# Power.net
KiCad netlist of a schematic drawn in Altium Designer
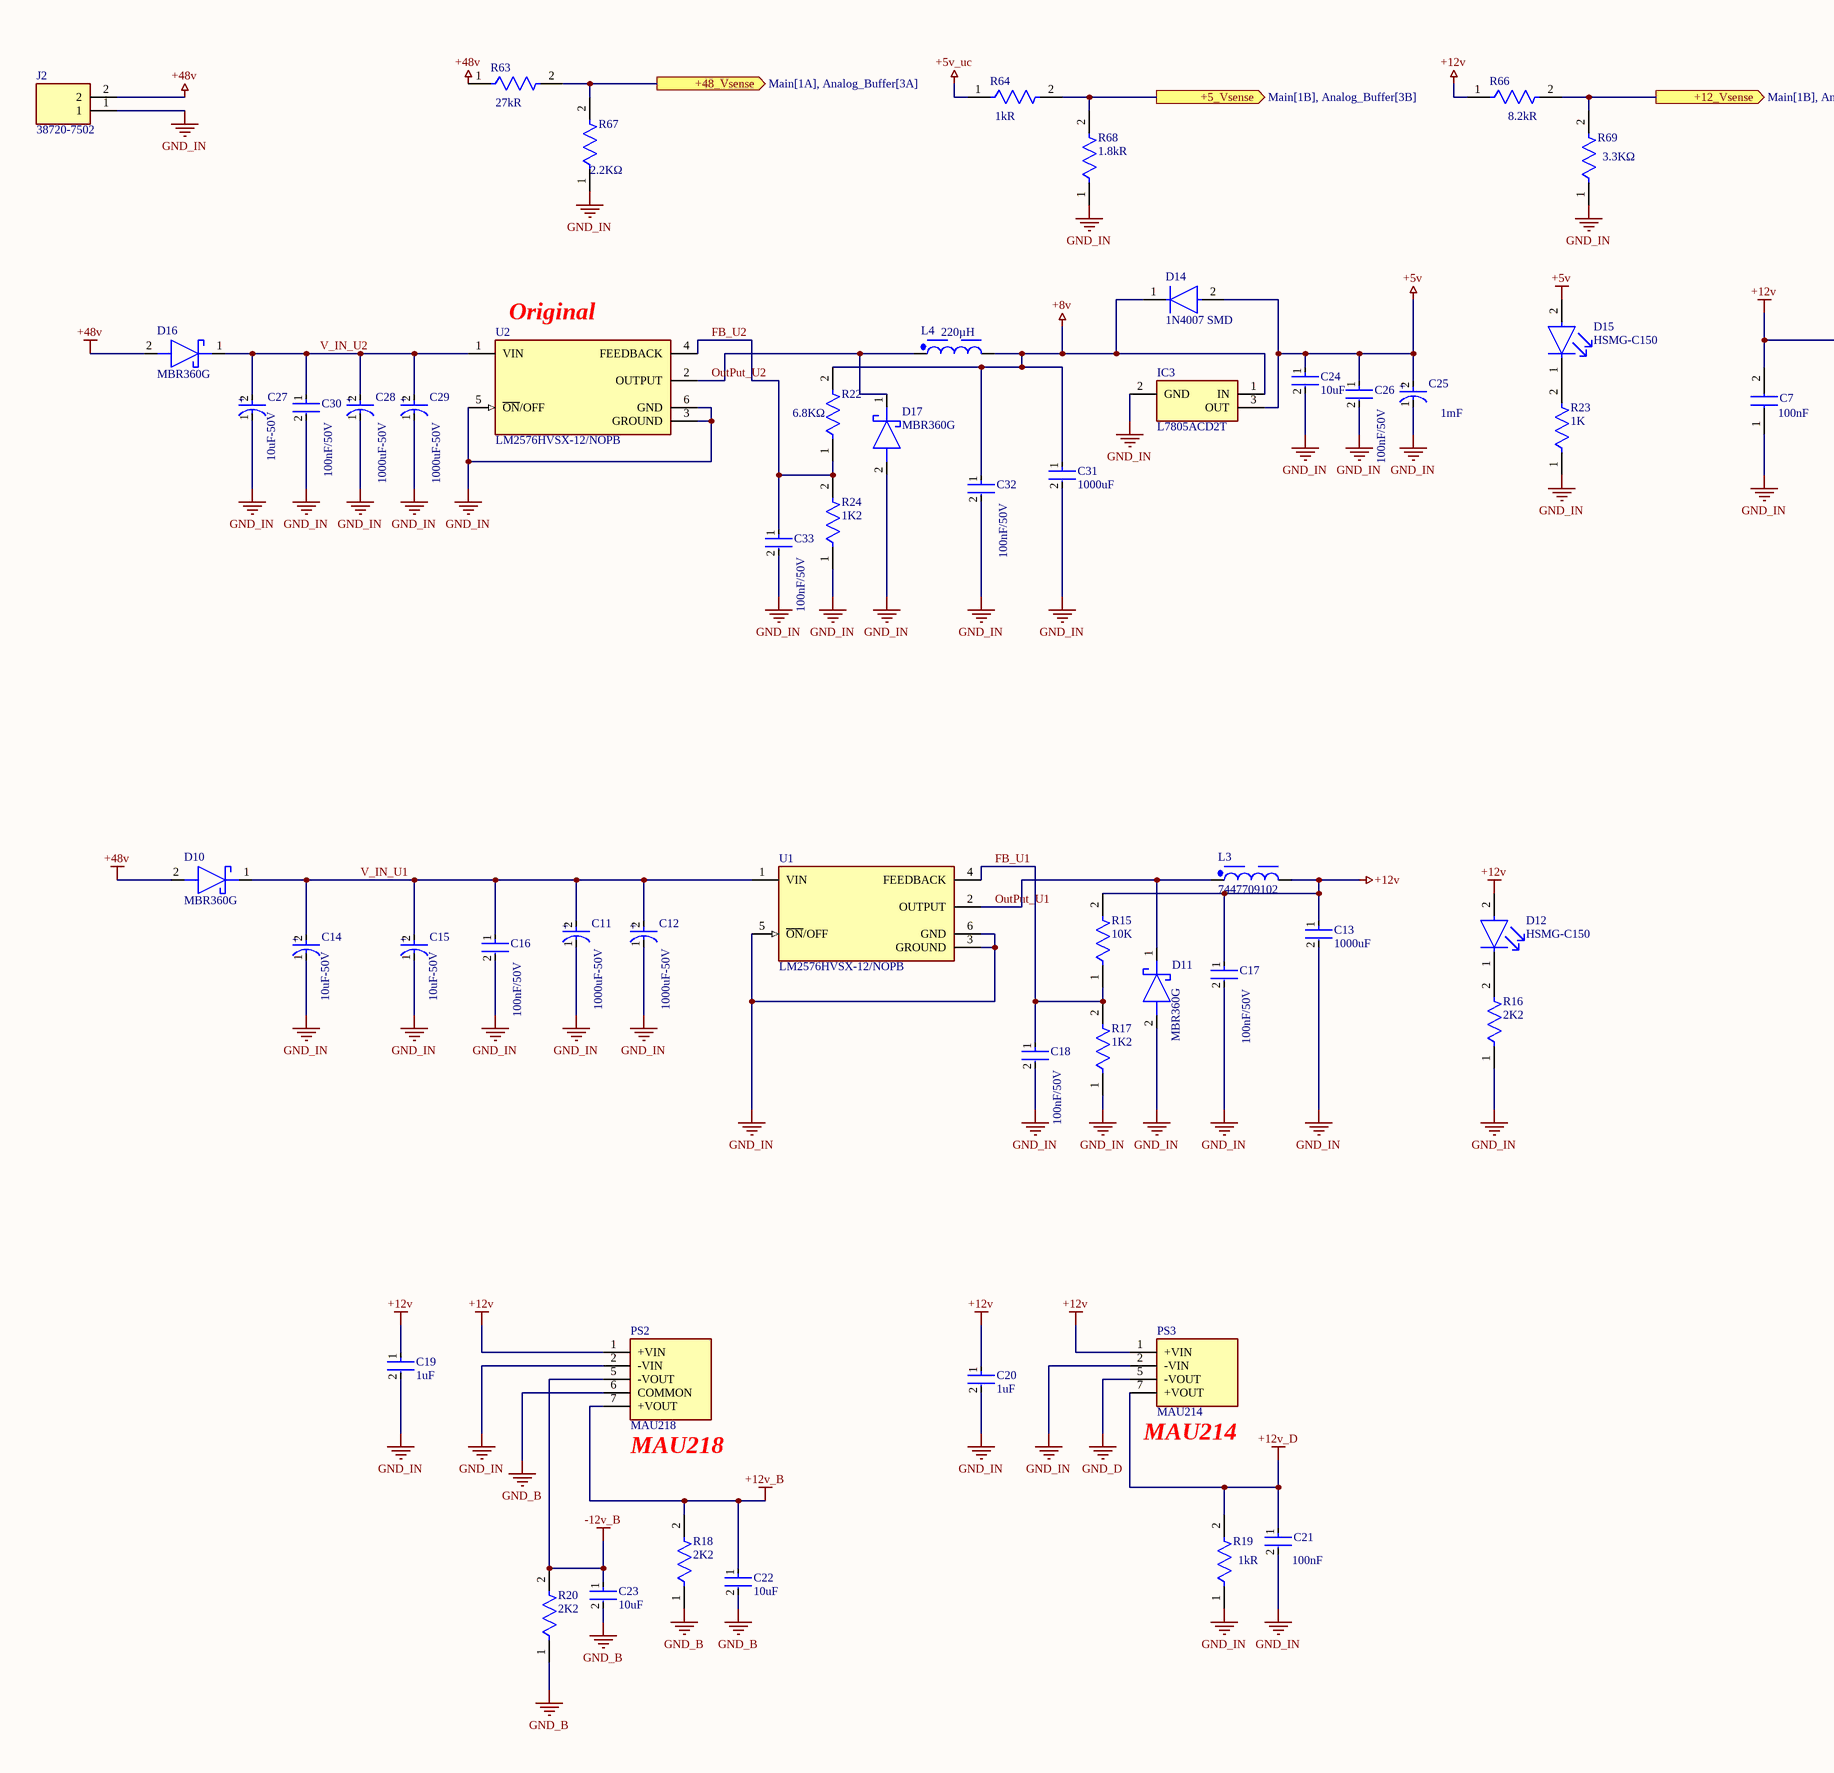
[diagram p0: Power.SchDoc, left]
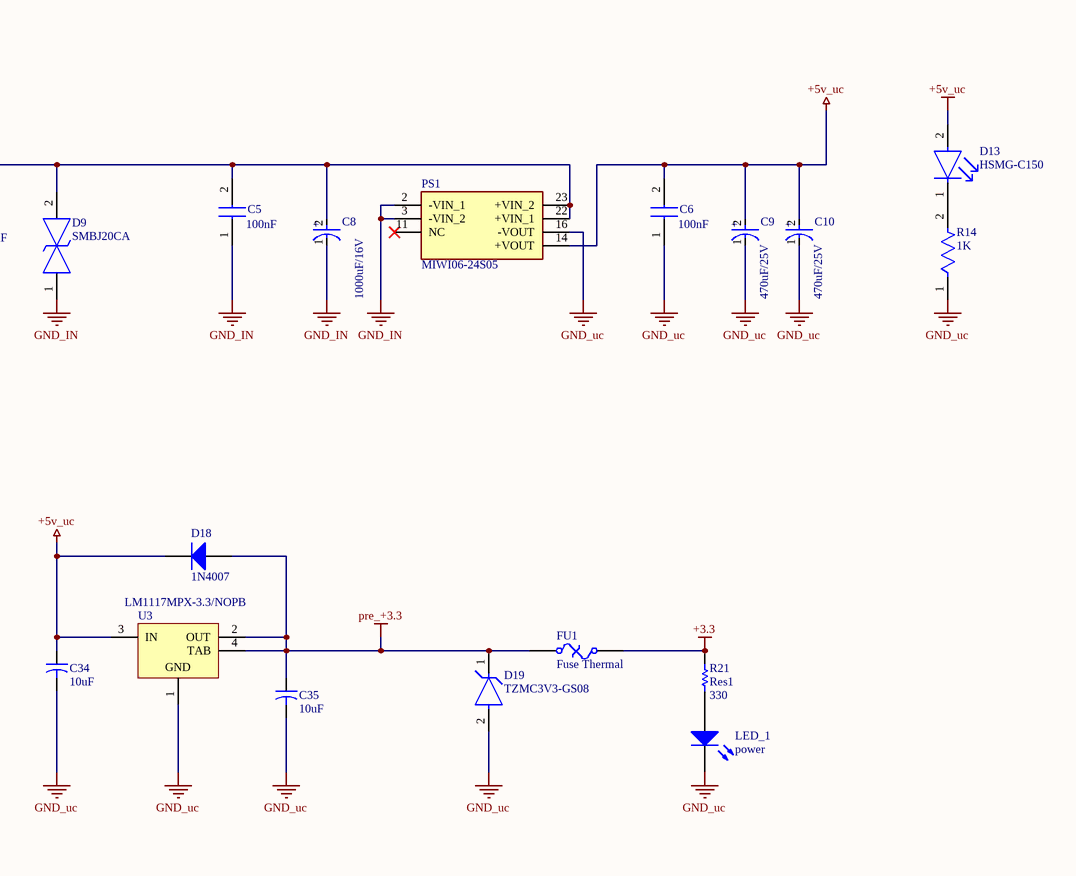
[diagram p1: Power.SchDoc, right]

(export (version "E")
  (design (tool "Eeschema 10.0.6"))
  (components
    (comp (ref "C5")
      (value "100nF")
      (footprint "SamacSys:CAPC3216X95N")
      (description "Capacitor")
      (fields
        (field (name "MANUFACTURER_PART_NUMBER") "GRM319F51H104ZA01D")
        (field (name "MOUSER PART NUMBER") "81-GRM319F51H104ZA")
      )
      (libsource (lib "*") (part "GRM319F51H104ZA01D"))
    )
    (comp (ref "C6")
      (value "100nF")
      (footprint "SamacSys:CAPC3216X95N")
      (description "Capacitor")
      (fields
        (field (name "MANUFACTURER_PART_NUMBER") "GRM319F51H104ZA01D")
        (field (name "MOUSER PART NUMBER") "81-GRM319F51H104ZA")
      )
      (libsource (lib "*") (part "GRM319F51H104ZA01D"))
    )
    (comp (ref "C7")
      (value "100nF")
      (footprint "SamacSys:CAPC3216X95N")
      (description "Capacitor")
      (fields
        (field (name "MANUFACTURER_PART_NUMBER") "GRM319F51H104ZA01D")
        (field (name "MOUSER PART NUMBER") "81-GRM319F51H104ZA")
      )
      (libsource (lib "*") (part "GRM319F51H104ZA01D"))
    )
    (comp (ref "C8")
      (value "1000uF/16V")
      (footprint "FP-FTG-MFG")
      (description "CAP ALUM 1000UF 20% 16V SMD")
      (fields (field (name "TOLERANCE") "20%") (field (name "VOLTAGE") "16V"))
      (libsource (lib "Altium Content Vault") (part "a00bbbee19879c290e62620ae7e47b1"))
    )
    (comp (ref "C9")
      (value "470uF/25V")
      (footprint "FP-FTF-MFG")
      (description "CAP ALUM 470UF 20% 25V SMD")
      (fields (field (name "VOLTAGE") "25V") (field (name "TOLERANCE") "20%"))
      (libsource (lib "Altium Content Vault") (part "a00bbbee19879c290e62620ae7e47b1"))
    )
    (comp (ref "C10")
      (value "470uF/25V")
      (footprint "FP-FTF-MFG")
      (description "CAP ALUM 470UF 20% 25V SMD")
      (fields (field (name "VOLTAGE") "25V") (field (name "TOLERANCE") "20%"))
      (libsource (lib "Altium Content Vault") (part "a00bbbee19879c290e62620ae7e47b1"))
    )
    (comp (ref "C11")
      (value "1000uF-50V")
      (footprint "FP-RAD-TH-D_12_5_0_5-L_25-MFG")
      (description "Aluminum Electrolytic Capacitors (Radial Lead Type) 1000uF ±20% 50V")
      (fields (field (name "TOLERANCE") "20%"))
      (libsource (lib "Altium Content Vault") (part "203bc49f2ac43e59fd269a8c329ed05"))
    )
    (comp (ref "C12")
      (value "1000uF-50V")
      (footprint "FP-RAD-TH-D_12_5_0_5-L_25-MFG")
      (description "Aluminum Electrolytic Capacitors (Radial Lead Type) 1000uF ±20% 50V")
      (fields (field (name "TOLERANCE") "20%"))
      (libsource (lib "Altium Content Vault") (part "203bc49f2ac43e59fd269a8c329ed05"))
    )
    (comp (ref "C13")
      (value "1000uF")
      (footprint "FP-C1206C-EB-MFG")
      (description "CAP CER 0.1UF 200V 10% X7R 1206")
      (fields (field (name "TOLERANCE") "0.1") (field (name "MANUFACTURER PART NUMBER") "C1206C104K2RACTU"))
      (libsource (lib "Altium Content Vault") (part "b4654b650e69147ec39a6b967a45e02"))
    )
    (comp (ref "C14")
      (value "10uF-50V")
      (footprint "FP-FKD-MFG")
      (description "CAP ALUM 10UF 20% 50V SMD")
      (fields (field (name "VOLTAGE") "50V") (field (name "TOLERANCE") "20%"))
      (libsource (lib "Altium Content Vault") (part "203bc49f2ac43e59fd269a8c329ed05"))
    )
    (comp (ref "C15")
      (value "10uF-50V")
      (footprint "FP-FKD-MFG")
      (description "CAP ALUM 10UF 20% 50V SMD")
      (fields (field (name "VOLTAGE") "50V") (field (name "TOLERANCE") "20%"))
      (libsource (lib "Altium Content Vault") (part "203bc49f2ac43e59fd269a8c329ed05"))
    )
    (comp (ref "C16")
      (value "100nF/50V")
      (footprint "FP-1206-L_3_2_0_2-W_1_6_0-MFG")
      (description "General Purpose Ceramic Capacitor, 1206, 100nF, 50V")
      (fields (field (name "TOLERANCE") "10%") (field (name "VOLTAGE") "50V"))
      (libsource (lib "Altium Content Vault") (part "02cd4be3c70576c341d710602a673aa"))
    )
    (comp (ref "C17")
      (value "100nF/50V")
      (footprint "FP-1206-L_3_2_0_2-W_1_6_0-MFG")
      (description "General Purpose Ceramic Capacitor, 1206, 100nF, 50V")
      (fields (field (name "TOLERANCE") "10%") (field (name "VOLTAGE") "50V"))
      (libsource (lib "Altium Content Vault") (part "02cd4be3c70576c341d710602a673aa"))
    )
    (comp (ref "C18")
      (value "100nF/50V")
      (footprint "FP-1206-L_3_2_0_2-W_1_6_0-MFG")
      (description "General Purpose Ceramic Capacitor, 1206, 100nF, 50V")
      (fields (field (name "TOLERANCE") "10%") (field (name "VOLTAGE") "50V"))
      (libsource (lib "Altium Content Vault") (part "02cd4be3c70576c341d710602a673aa"))
    )
    (comp (ref "C19")
      (value "1uF")
      (footprint "FP-1206-L_3_2_0_2-W_1_6_0-IPC_A")
      (description "General Purpose Ceramic Capacitor, 1206, 1uF, 10%, X7R, 15%, 50V")
      (fields (field (name "TOLERANCE") "10%") (field (name "VOLTAGE") "25V"))
      (libsource (lib "Altium Content Vault") (part "b4654b650e69147ec39a6b967a45e02"))
    )
    (comp (ref "C20")
      (value "1uF")
      (footprint "FP-1206-L_3_2_0_2-W_1_6_0-IPC_A")
      (description "General Purpose Ceramic Capacitor, 1206, 1uF, 10%, X7R, 15%, 50V")
      (fields (field (name "TOLERANCE") "10%") (field (name "VOLTAGE") "25V"))
      (libsource (lib "Altium Content Vault") (part "b4654b650e69147ec39a6b967a45e02"))
    )
    (comp (ref "C21")
      (value "12065C104KAT2A")
      (footprint "FP-1206-L_3_2_0_2-W_1_6_0-MFG")
      (description "General Purpose Ceramic Capacitor, 1206, 100nF, 10%, X7R, 15%, 50V")
      (fields
        (field (name "TOLERANCE") "10%")
        (field (name "VOLTAGE") "50V")
        (field (name "CAPACITANCE") "100nF")
      )
      (libsource (lib "Altium Content Vault") (part "02cd4be3c70576c341d710602a673aa"))
    )
    (comp (ref "C22")
      (value "10uF")
      (footprint "FP-GRM31C-0_2-e0_3_0_8-MFG")
      (description "Chip Multilayer Ceramic Capacitors for General Purpose, 1206, 10uF, X7R, 15%, 10%, 25V")
      (fields (field (name "TOLERANCE") "10%") (field (name "VOLTAGE") "25V"))
      (libsource (lib "Altium Content Vault") (part "02cd4be3c70576c341d710602a673aa"))
    )
    (comp (ref "C23")
      (value "10uF")
      (footprint "FP-GRM31C-0_2-e0_3_0_8-MFG")
      (description "Chip Multilayer Ceramic Capacitors for General Purpose, 1206, 10uF, X7R, 15%, 10%, 25V")
      (fields (field (name "TOLERANCE") "10%") (field (name "VOLTAGE") "25V"))
      (libsource (lib "Altium Content Vault") (part "02cd4be3c70576c341d710602a673aa"))
    )
    (comp (ref "C24")
      (value "10uF")
      (footprint "FP-GRM31C-0_2-e0_3_0_8-MFG")
      (description "Chip Multilayer Ceramic Capacitors for General Purpose, 1206, 10uF, X7R, 15%, 10%, 25V")
      (fields (field (name "TOLERANCE") "10%") (field (name "VOLTAGE") "25V"))
      (libsource (lib "Altium Content Vault") (part "02cd4be3c70576c341d710602a673aa"))
    )
    (comp (ref "C25")
      (value "EEEFT1C102AP")
      (footprint "FP-FTG-MFG")
      (description "CAP ALUM 1000UF 20% 16V SMD")
      (fields
        (field (name "TOLERANCE") "20%")
        (field (name "CAPACITANCE") "1mF")
        (field (name "VOLTAGE") "16V")
      )
      (libsource (lib "Altium Content Vault") (part "a00bbbee19879c290e62620ae7e47b1"))
    )
    (comp (ref "C26")
      (value "100nF/50V")
      (footprint "FP-1206-L_3_2_0_2-W_1_6_0-MFG")
      (description "General Purpose Ceramic Capacitor, 1206, 100nF, 50V")
      (fields (field (name "TOLERANCE") "10%") (field (name "VOLTAGE") "50V"))
      (libsource (lib "Altium Content Vault") (part "02cd4be3c70576c341d710602a673aa"))
    )
    (comp (ref "C27")
      (value "10uF-50V")
      (footprint "FP-FKD-MFG")
      (description "CAP ALUM 10UF 20% 50V SMD")
      (fields (field (name "VOLTAGE") "50V") (field (name "TOLERANCE") "20%"))
      (libsource (lib "Altium Content Vault") (part "203bc49f2ac43e59fd269a8c329ed05"))
    )
    (comp (ref "C28")
      (value "1000uF-50V")
      (footprint "FP-RAD-TH-D_12_5_0_5-L_25-MFG")
      (description "Aluminum Electrolytic Capacitors (Radial Lead Type) 1000uF ±20% 50V")
      (fields (field (name "TOLERANCE") "20%"))
      (libsource (lib "Altium Content Vault") (part "203bc49f2ac43e59fd269a8c329ed05"))
    )
    (comp (ref "C29")
      (value "1000uF-50V")
      (footprint "FP-RAD-TH-D_12_5_0_5-L_25-MFG")
      (description "Aluminum Electrolytic Capacitors (Radial Lead Type) 1000uF ±20% 50V")
      (fields (field (name "TOLERANCE") "20%"))
      (libsource (lib "Altium Content Vault") (part "203bc49f2ac43e59fd269a8c329ed05"))
    )
    (comp (ref "C30")
      (value "100nF/50V")
      (footprint "FP-1206-L_3_2_0_2-W_1_6_0-MFG")
      (description "General Purpose Ceramic Capacitor, 1206, 100nF, 50V")
      (fields (field (name "TOLERANCE") "10%") (field (name "VOLTAGE") "50V"))
      (libsource (lib "Altium Content Vault") (part "02cd4be3c70576c341d710602a673aa"))
    )
    (comp (ref "C31")
      (value "1000uF")
      (footprint "FP-C1206C-EB-MFG")
      (description "CAP CER 0.1UF 200V 10% X7R 1206")
      (fields (field (name "TOLERANCE") "0.1") (field (name "MANUFACTURER PART NUMBER") "C1206C104K2RACTU"))
      (libsource (lib "Altium Content Vault") (part "b4654b650e69147ec39a6b967a45e02"))
    )
    (comp (ref "C32")
      (value "100nF/50V")
      (footprint "FP-1206-L_3_2_0_2-W_1_6_0-MFG")
      (description "General Purpose Ceramic Capacitor, 1206, 100nF, 50V")
      (fields (field (name "TOLERANCE") "10%") (field (name "VOLTAGE") "50V"))
      (libsource (lib "Altium Content Vault") (part "02cd4be3c70576c341d710602a673aa"))
    )
    (comp (ref "C33")
      (value "100nF/50V")
      (footprint "FP-1206-L_3_2_0_2-W_1_6_0-MFG")
      (description "General Purpose Ceramic Capacitor, 1206, 100nF, 50V")
      (fields (field (name "TOLERANCE") "10%") (field (name "VOLTAGE") "50V"))
      (libsource (lib "Altium Content Vault") (part "02cd4be3c70576c341d710602a673aa"))
    )
    (comp (ref "C34")
      (value "10uF")
      (footprint "0805C")
      (description "Capacitor")
      (fields (field (name "Comment") "Cap_El") (field (name "PUBLISHER") "Altium Limited"))
      (libsource (lib "KN2CLib") (part "Cap_El"))
    )
    (comp (ref "C35")
      (value "10uF")
      (footprint "0805C")
      (description "Capacitor")
      (fields (field (name "Comment") "Cap_El") (field (name "PUBLISHER") "Altium Limited"))
      (libsource (lib "KN2CLib") (part "Cap_El"))
    )
    (comp (ref "D9")
      (value "SMBJ20CA")
      (footprint "SamacSys:DIOM5336X245N")
      (description "TVS Diode (Bi-directional)")
      (fields (field (name "MOUSER PART NUMBER") "512-SMBJ20CA"))
      (libsource (lib "*") (part "SMBJ20CA"))
    )
    (comp (ref "D10")
      (value "MBR360G")
      (footprint "SamacSys:DIOAD2860W130L840D505")
      (description "Schottky Diode")
      (fields (field (name "MOUSER PART NUMBER") "863-MBR360G"))
      (libsource (lib "*") (part "MBR360G"))
    )
    (comp (ref "D11")
      (value "MBR360G")
      (footprint "SamacSys:DIOAD2860W130L840D505")
      (description "Schottky Diode")
      (fields (field (name "MOUSER PART NUMBER") "863-MBR360G"))
      (libsource (lib "*") (part "MBR360G"))
    )
    (comp (ref "D12")
      (value "HSMG-C150")
      (footprint "FP-HSMG-C150-MFG")
      (description "LED GREEN DIFFUSED 1206 SMD")
      (fields
        (field (name "MANUFACTURER") "Broadcom")
        (field (name "OCTOPART") "https://octopart.com/hsmg-c150-broadcom-71131304")
      )
      (libsource (lib "Altium Content Vault") (part "8706943c75ba83719d021d2fdc84c58"))
    )
    (comp (ref "D13")
      (value "HSMG-C150")
      (footprint "FP-HSMG-C150-MFG")
      (description "LED GREEN DIFFUSED 1206 SMD")
      (fields
        (field (name "MANUFACTURER") "Broadcom")
        (field (name "OCTOPART") "https://octopart.com/hsmg-c150-broadcom-71131304")
      )
      (libsource (lib "Altium Content Vault") (part "8706943c75ba83719d021d2fdc84c58"))
    )
    (comp (ref "D14")
      (value "1N4007 SMD")
      (footprint "FP-1N4007_SMD-IPC_C")
      (description "Rectifier, 1Kv, 1A, Do-214Ac Rohs Compliant: Yes")
      (libsource (lib "Altium Content Vault") (part "d7152d700b627762746794eb795d46e"))
    )
    (comp (ref "D15")
      (value "HSMG-C150")
      (footprint "FP-HSMG-C150-MFG")
      (description "LED GREEN DIFFUSED 1206 SMD")
      (fields
        (field (name "MANUFACTURER") "Broadcom")
        (field (name "OCTOPART") "https://octopart.com/hsmg-c150-broadcom-71131304")
      )
      (libsource (lib "Altium Content Vault") (part "8706943c75ba83719d021d2fdc84c58"))
    )
    (comp (ref "D16")
      (value "MBR360G")
      (footprint "SamacSys:DIOAD2860W130L840D505")
      (description "Schottky Diode")
      (fields (field (name "MOUSER PART NUMBER") "863-MBR360G"))
      (libsource (lib "*") (part "MBR360G"))
    )
    (comp (ref "D17")
      (value "MBR360G")
      (footprint "SamacSys:DIOAD2860W130L840D505")
      (description "Schottky Diode")
      (fields (field (name "MOUSER PART NUMBER") "863-MBR360G"))
      (libsource (lib "*") (part "MBR360G"))
    )
    (comp (ref "D18")
      (value "1N4007")
      (footprint "430X270D")
      (description "1 Amp General Purpose Rectifier")
      (fields (field (name "PUBLISHER") "Altium Limited"))
      (libsource (lib "KN2CLib") (part "Diode"))
    )
    (comp (ref "D19")
      (value "TZMC3V3-GS08")
      (footprint "FP-6_560-5005_01-4-MFG")
      (description "DIODE ZENER 3.3V 500MW SOD80")
      (fields
        (field (name "MANUFACTURER") "Vishay")
        (field (name "OCTOPART") "https://octopart.com/tzmc3v3-gs08-vishay-55388698")
      )
      (libsource (lib "Altium Content Vault") (part "f813f71cba58e380607f5dd3caf9714"))
    )
    (comp (ref "FU1")
      (value "Fuse Thermal")
      (footprint "1206")
      (description "Thermal Fuse")
      (fields (field (name "PUBLISHER") "Altium Limited"))
      (libsource (lib "Miscellaneous Devices") (part "Fuse Thermal"))
    )
    (comp (ref "IC3")
      (value "L7805ACD2T")
      (footprint "SamacSys:STB20N95K5")
      (description "Integrated Circuit")
      (fields (field (name "MOUSER PART NUMBER") "511-L7805ACD2T"))
      (libsource (lib "*") (part "L7805ACD2T"))
    )
    (comp (ref "J2")
      (value "38720-7502")
      (footprint "SamacSys:387207502")
      (description "Connector")
      (fields (field (name "MOUSER PART NUMBER") "538-38720-7502"))
      (libsource (lib "*") (part "38720-7502"))
    )
    (comp (ref "L3")
      (value "7447709102")
      (footprint "WE-PD_1210")
      (fields (field (name "TOLERANCE") "20%"))
      (libsource (lib "Altium Content Vault") (part "Inductor - 2"))
    )
    (comp (ref "L4")
      (value "7447709221")
      (footprint "WE-PD_1210")
      (fields (field (name "INDUCTANCE") "220µH") (field (name "TOLERANCE") "20%"))
      (libsource (lib "Altium Content Vault") (part "Inductor - 2"))
    )
    (comp (ref "LED_1")
      (value "power")
      (footprint "0805LED")
      (description "Typical BLUE SiC LED")
      (fields (field (name "PUBLISHER") "Altium Limited"))
      (libsource (lib "Miscellaneous Devices") (part "LED3"))
    )
    (comp (ref "PS1")
      (value "MIWI06-24S05")
      (footprint "SamacSys:MIWI06_S")
      (description "Power Supply")
      (libsource (lib "*") (part "MIWI06-24S05"))
    )
    (comp (ref "PS2")
      (value "MAU218")
      (footprint "SamacSys:MAU218")
      (description "Power Supply")
      (libsource (lib "*") (part "MAU218"))
    )
    (comp (ref "PS3")
      (value "MAU214")
      (footprint "SamacSys:MAU214")
      (description "Power Supply")
      (libsource (lib "*") (part "MAU214"))
    )
    (comp (ref "R14")
      (value "1K")
      (footprint "FP-CR1206-IPC_A")
      (description "Thick Film Chip Resistors 1206 1kΩ 0.25W 1% 100ppm/°C")
      (fields (field (name "TOLERANCE") "1%"))
      (libsource (lib "Altium Content Vault") (part "1029c3af85768c4190bb7ad29bc67b5"))
    )
    (comp (ref "R15")
      (value "10K")
      (footprint "FP-CRCW1206-e3-IPC_C")
      (description "RES Thick Film, 10kΩ, 1%, 0.25W, 100ppm/°C, 1206")
      (fields (field (name "TOLERANCE") "1%"))
      (libsource (lib "Altium Content Vault") (part "1029c3af85768c4190bb7ad29bc67b5"))
    )
    (comp (ref "R16")
      (value "2K2")
      (footprint "FP-CRGCQ1206-IPC_C")
      (description "CRGCQ 1206 2K2 5%")
      (fields (field (name "TOLERANCE") "0.05") (field (name "MANUFACTURER PART NUMBER") "CRGCQ1206J2K2"))
      (libsource (lib "Altium Content Vault") (part "1029c3af85768c4190bb7ad29bc67b5"))
    )
    (comp (ref "R17")
      (value "1K2")
      (footprint "FP-CRGCQ1206-IPC_C")
      (description "CRGCQ 1206 1K2 1%")
      (fields
        (field (name "MANUFACTURER") "TE Connectivity")
        (field (name "OCTOPART") "https://octopart.com/crgcq1206f1k2-te+connectivity-91018259")
      )
      (libsource (lib "Altium Content Vault") (part "1029c3af85768c4190bb7ad29bc67b5"))
    )
    (comp (ref "R18")
      (value "2K2")
      (footprint "FP-CRGCQ1206-IPC_C")
      (description "CRGCQ 1206 2K2 5%")
      (fields (field (name "TOLERANCE") "0.05") (field (name "MANUFACTURER PART NUMBER") "CRGCQ1206J2K2"))
      (libsource (lib "Altium Content Vault") (part "1029c3af85768c4190bb7ad29bc67b5"))
    )
    (comp (ref "R19")
      (value "CR1206-FX-1001ELF")
      (footprint "FP-CR1206-IPC_A")
      (description "Thick Film Chip Resistors 1206 1kΩ 0.25W 1% 100ppm/°C")
      (fields (field (name "TOLERANCE") "1%") (field (name "RESISTANCE") "1kR"))
      (libsource (lib "Altium Content Vault") (part "1029c3af85768c4190bb7ad29bc67b5"))
    )
    (comp (ref "R20")
      (value "2K2")
      (footprint "FP-CRGCQ1206-IPC_C")
      (description "CRGCQ 1206 2K2 5%")
      (fields (field (name "TOLERANCE") "0.05") (field (name "MANUFACTURER PART NUMBER") "CRGCQ1206J2K2"))
      (libsource (lib "Altium Content Vault") (part "1029c3af85768c4190bb7ad29bc67b5"))
    )
    (comp (ref "R21")
      (value "Res1")
      (footprint "0805L")
      (description "Resistor")
      (fields (field (name "ALTIUM_VALUE") "330") (field (name "PUBLISHER") "Altium Limited"))
      (libsource (lib "Miscellaneous Devices") (part "Res1"))
    )
    (comp (ref "R22")
      (value "6.8KΩ")
      (footprint "FP-CRGCQ1206-IPC_C")
      (description "CRGCQ1206 6.8KΩ 0.25W 5% ±100ppm/°C 200V")
      (fields
        (field (name "TOLERANCE") "0.05")
        (field (name "OCTOPART") "https://octopart.com/crgcq1206j6k8-te+connectivity-91018343")
      )
      (libsource (lib "Altium Content Vault") (part "1029c3af85768c4190bb7ad29bc67b5"))
    )
    (comp (ref "R23")
      (value "1K")
      (footprint "FP-CR1206-IPC_A")
      (description "Thick Film Chip Resistors 1206 1kΩ 0.25W 1% 100ppm/°C")
      (fields (field (name "TOLERANCE") "1%"))
      (libsource (lib "Altium Content Vault") (part "1029c3af85768c4190bb7ad29bc67b5"))
    )
    (comp (ref "R24")
      (value "1K2")
      (footprint "FP-CRGCQ1206-IPC_C")
      (description "CRGCQ 1206 1K2 1%")
      (fields
        (field (name "MANUFACTURER") "TE Connectivity")
        (field (name "OCTOPART") "https://octopart.com/crgcq1206f1k2-te+connectivity-91018259")
      )
      (libsource (lib "Altium Content Vault") (part "1029c3af85768c4190bb7ad29bc67b5"))
    )
    (comp (ref "R63")
      (value "RC3216J273CS")
      (footprint "FP-RC3216-IPC_A")
      (description "Res Thick Film 1206 27kΩ 5% 0.25W ±100ppm/°C Molded SMD T/R")
      (fields (field (name "TOLERANCE") "5%") (field (name "RESISTANCE") "27kR"))
      (libsource (lib "Altium Content Vault") (part "1029c3af85768c4190bb7ad29bc67b5"))
    )
    (comp (ref "R64")
      (value "CR1206-FX-1001ELF")
      (footprint "FP-CR1206-IPC_A")
      (description "Thick Film Chip Resistors 1206 1kΩ 0.25W 1% 100ppm/°C")
      (fields (field (name "TOLERANCE") "1%") (field (name "RESISTANCE") "1kR"))
      (libsource (lib "Altium Content Vault") (part "1029c3af85768c4190bb7ad29bc67b5"))
    )
    (comp (ref "R66")
      (value "CRCW12068K20FKEA")
      (footprint "FP-CRCW1206-e3-IPC_A")
      (description "RES Thick Film, 8.2kΩ, 1%, 0.25W, 100ppm/°C, 1206")
      (fields (field (name "TOLERANCE") "1%") (field (name "RESISTANCE") "8.2kR"))
      (libsource (lib "Altium Content Vault") (part "1029c3af85768c4190bb7ad29bc67b5"))
    )
    (comp (ref "R67")
      (value "2.2KΩ")
      (footprint "FP-CRGCQ1206-IPC_C")
      (description "CRGCQ 1206 2K2 5%")
      (fields (field (name "TOLERANCE") "0.05") (field (name "MANUFACTURER PART NUMBER") "CRGCQ1206J2K2"))
      (libsource (lib "Altium Content Vault") (part "1029c3af85768c4190bb7ad29bc67b5"))
    )
    (comp (ref "R68")
      (value "CRCW12061K80FKEA")
      (footprint "FP-CRCW1206-e3-IPC_B")
      (description "RES Thick Film, 1.8kΩ, 1%, 0.25W, 100ppm/°C, 1206")
      (fields (field (name "RESISTANCE") "1.8kR") (field (name "TOLERANCE") "1%"))
      (libsource (lib "Altium Content Vault") (part "1029c3af85768c4190bb7ad29bc67b5"))
    )
    (comp (ref "R69")
      (value "3.3KΩ")
      (footprint "FP-CRGCQ1206-IPC_C")
      (description "CRGCQ1206 3.3KΩ 0.25W 5% ±100ppm/°C 200V")
      (fields
        (field (name "OCTOPART") "https://octopart.com/crgcq1206j3k3-te+connectivity-91018329")
        (field (name "MANUFACTURER PART NUMBER") "CRGCQ1206J3K3")
      )
      (libsource (lib "Altium Content Vault") (part "1029c3af85768c4190bb7ad29bc67b5"))
    )
    (comp (ref "U1")
      (value "LM2576HVSX-12/NOPB")
      (footprint "FP-KTT0005B-MFG")
      (description "IC REG BUCK 12V 3A TO263-5")
      (libsource (lib "Altium Content Vault") (part "970efae79796d18f90998b1df728a7c"))
    )
    (comp (ref "U2")
      (value "LM2576HVSX-12/NOPB")
      (footprint "FP-KTT0005B-MFG")
      (description "IC REG BUCK 12V 3A TO263-5")
      (libsource (lib "Altium Content Vault") (part "970efae79796d18f90998b1df728a7c"))
    )
    (comp (ref "U3")
      (value "LM1117MPX-3.3/NOPB")
      (footprint "DCY0004A_L")
      (description "800mA Low-Dropout Linear Regulator, 4-pin SOT-223, Pb-Free")
      (fields (field (name "MANUFACTURER") "Texas Instruments"))
      (libsource (lib "Altium Content Vault") (part "PM-REG-LM1086-SOT4"))
    )
  )
  (nets
    (net (code "1") (name "+3.3") (class "Default")
      (node (ref "FU1") (pin "2") (pinfunction "2_2") (pintype "passive"))
      (node (ref "R21") (pin "1") (pinfunction "1_1") (pintype "passive"))
    )
    (net (code "2") (name "+5v") (class "Default")
      (node (ref "C24") (pin "1") (pinfunction "1_1") (pintype "passive"))
      (node (ref "C25") (pin "2") (pinfunction "A_2") (pintype "passive"))
      (node (ref "C26") (pin "1") (pinfunction "1_1") (pintype "passive"))
      (node (ref "D14") (pin "2") (pinfunction "A_2") (pintype "passive"))
      (node (ref "D15") (pin "2") (pinfunction "A_2") (pintype "passive"))
      (node (ref "IC3") (pin "3") (pinfunction "OUT_3") (pintype "passive"))
    )
    (net (code "3") (name "+5v_uc") (class "Default")
      (node (ref "C10") (pin "2") (pinfunction "A_2") (pintype "passive"))
      (node (ref "C34") (pin "1") (pinfunction "1_1") (pintype "passive"))
      (node (ref "C6") (pin "2") (pinfunction "2_2") (pintype "passive"))
      (node (ref "C9") (pin "2") (pinfunction "A_2") (pintype "passive"))
      (node (ref "D13") (pin "2") (pinfunction "A_2") (pintype "passive"))
      (node (ref "D18") (pin "2") (pinfunction "K_2") (pintype "passive"))
      (node (ref "PS1") (pin "14") (pinfunction "+VOUT_14") (pintype "passive"))
      (node (ref "R64") (pin "1") (pinfunction "1_1") (pintype "passive"))
      (node (ref "U3") (pin "3") (pinfunction "IN_3") (pintype "power_in"))
    )
    (net (code "4") (name "+8v") (class "Default")
      (node (ref "C31") (pin "1") (pinfunction "1_1") (pintype "passive"))
      (node (ref "C32") (pin "1") (pinfunction "1_1") (pintype "passive"))
      (node (ref "D14") (pin "1") (pinfunction "C_1") (pintype "passive"))
      (node (ref "IC3") (pin "1") (pinfunction "IN_1") (pintype "passive"))
      (node (ref "L4") (pin "2") (pinfunction "2_2") (pintype "passive"))
      (node (ref "R22") (pin "2") (pinfunction "2_2") (pintype "passive"))
    )
    (net (code "5") (name "+12v") (class "Default")
      (node (ref "C13") (pin "1") (pinfunction "1_1") (pintype "passive"))
      (node (ref "C17") (pin "1") (pinfunction "1_1") (pintype "passive"))
      (node (ref "C19") (pin "1") (pinfunction "1_1") (pintype "passive"))
      (node (ref "C20") (pin "1") (pinfunction "1_1") (pintype "passive"))
      (node (ref "C5") (pin "2") (pinfunction "2_2") (pintype "passive"))
      (node (ref "C7") (pin "2") (pinfunction "2_2") (pintype "passive"))
      (node (ref "C8") (pin "2") (pinfunction "A_2") (pintype "passive"))
      (node (ref "D12") (pin "2") (pinfunction "A_2") (pintype "passive"))
      (node (ref "D9") (pin "2") (pinfunction "2_2") (pintype "passive"))
      (node (ref "L3") (pin "2") (pinfunction "2_2") (pintype "passive"))
      (node (ref "PS1") (pin "22") (pinfunction "+VIN_1_22") (pintype "passive"))
      (node (ref "PS1") (pin "23") (pinfunction "+VIN_2_23") (pintype "passive"))
      (node (ref "PS2") (pin "1") (pinfunction "+VIN_1") (pintype "passive"))
      (node (ref "PS3") (pin "1") (pinfunction "+VIN_1") (pintype "passive"))
      (node (ref "R15") (pin "2") (pinfunction "2_2") (pintype "passive"))
      (node (ref "R66") (pin "1") (pinfunction "1_1") (pintype "passive"))
    )
    (net (code "6") (name "+12v_B") (class "Default")
      (node (ref "C22") (pin "1") (pinfunction "1_1") (pintype "passive"))
      (node (ref "PS2") (pin "7") (pinfunction "+VOUT_7") (pintype "passive"))
      (node (ref "R18") (pin "2") (pinfunction "2_2") (pintype "passive"))
    )
    (net (code "7") (name "+12v_D") (class "Default")
      (node (ref "C21") (pin "1") (pinfunction "1_1") (pintype "passive"))
      (node (ref "PS3") (pin "7") (pinfunction "+VOUT_7") (pintype "passive"))
      (node (ref "R19") (pin "2") (pinfunction "2_2") (pintype "passive"))
    )
    (net (code "8") (name "+48v") (class "Default")
      (node (ref "D10") (pin "2") (pinfunction "A_2") (pintype "passive"))
      (node (ref "D16") (pin "2") (pinfunction "A_2") (pintype "passive"))
      (node (ref "J2") (pin "2") (pinfunction "2_2") (pintype "passive"))
      (node (ref "R63") (pin "1") (pinfunction "1_1") (pintype "passive"))
    )
    (net (code "9") (name "-12v_B") (class "Default")
      (node (ref "C23") (pin "1") (pinfunction "1_1") (pintype "passive"))
      (node (ref "PS2") (pin "5") (pinfunction "-VOUT_5") (pintype "passive"))
      (node (ref "R20") (pin "2") (pinfunction "2_2") (pintype "passive"))
    )
    (net (code "10") (name "/+5_Vsense") (class "Default")
      (node (ref "R64") (pin "2") (pinfunction "2_2") (pintype "passive"))
      (node (ref "R68") (pin "2") (pinfunction "2_2") (pintype "passive"))
    )
    (net (code "11") (name "/+12_Vsense") (class "Default")
      (node (ref "R66") (pin "2") (pinfunction "2_2") (pintype "passive"))
      (node (ref "R69") (pin "2") (pinfunction "2_2") (pintype "passive"))
    )
    (net (code "12") (name "/+48_Vsense") (class "Default")
      (node (ref "R63") (pin "2") (pinfunction "2_2") (pintype "passive"))
      (node (ref "R67") (pin "2") (pinfunction "2_2") (pintype "passive"))
    )
    (net (code "13") (name "/FB_U1") (class "Default")
      (node (ref "C18") (pin "1") (pinfunction "1_1") (pintype "passive"))
      (node (ref "R15") (pin "1") (pinfunction "1_1") (pintype "passive"))
      (node (ref "R17") (pin "2") (pinfunction "2_2") (pintype "passive"))
      (node (ref "U1") (pin "4") (pinfunction "FEEDBACK_4") (pintype "passive"))
    )
    (net (code "14") (name "/FB_U2") (class "Default")
      (node (ref "C33") (pin "1") (pinfunction "1_1") (pintype "passive"))
      (node (ref "R22") (pin "1") (pinfunction "1_1") (pintype "passive"))
      (node (ref "R24") (pin "2") (pinfunction "2_2") (pintype "passive"))
      (node (ref "U2") (pin "4") (pinfunction "FEEDBACK_4") (pintype "passive"))
    )
    (net (code "15") (name "/OutPut_U1") (class "Default")
      (node (ref "D11") (pin "1") (pinfunction "K_1") (pintype "passive"))
      (node (ref "L3") (pin "1") (pinfunction "1_1") (pintype "passive"))
      (node (ref "U1") (pin "2") (pinfunction "OUTPUT_2") (pintype "power_in"))
    )
    (net (code "16") (name "/OutPut_U2") (class "Default")
      (node (ref "D17") (pin "1") (pinfunction "K_1") (pintype "passive"))
      (node (ref "L4") (pin "1") (pinfunction "1_1") (pintype "passive"))
      (node (ref "U2") (pin "2") (pinfunction "OUTPUT_2") (pintype "power_in"))
    )
    (net (code "17") (name "/V_IN_U1") (class "Default")
      (node (ref "C11") (pin "2") (pinfunction "A_2") (pintype "passive"))
      (node (ref "C12") (pin "2") (pinfunction "A_2") (pintype "passive"))
      (node (ref "C14") (pin "2") (pinfunction "A_2") (pintype "passive"))
      (node (ref "C15") (pin "2") (pinfunction "A_2") (pintype "passive"))
      (node (ref "C16") (pin "1") (pinfunction "1_1") (pintype "passive"))
      (node (ref "D10") (pin "1") (pinfunction "K_1") (pintype "passive"))
      (node (ref "U1") (pin "1") (pinfunction "VIN_1") (pintype "power_in"))
    )
    (net (code "18") (name "/V_IN_U2") (class "Default")
      (node (ref "C27") (pin "2") (pinfunction "A_2") (pintype "passive"))
      (node (ref "C28") (pin "2") (pinfunction "A_2") (pintype "passive"))
      (node (ref "C29") (pin "2") (pinfunction "A_2") (pintype "passive"))
      (node (ref "C30") (pin "1") (pinfunction "1_1") (pintype "passive"))
      (node (ref "D16") (pin "1") (pinfunction "K_1") (pintype "passive"))
      (node (ref "U2") (pin "1") (pinfunction "VIN_1") (pintype "power_in"))
    )
    (net (code "19") (name "GND_B") (class "Default")
      (node (ref "C22") (pin "2") (pinfunction "2_2") (pintype "passive"))
      (node (ref "C23") (pin "2") (pinfunction "2_2") (pintype "passive"))
      (node (ref "PS2") (pin "6") (pinfunction "COMMON_6") (pintype "passive"))
      (node (ref "R18") (pin "1") (pinfunction "1_1") (pintype "passive"))
      (node (ref "R20") (pin "1") (pinfunction "1_1") (pintype "passive"))
    )
    (net (code "20") (name "GND_D") (class "Default")
      (node (ref "PS3") (pin "5") (pinfunction "-VOUT_5") (pintype "passive"))
    )
    (net (code "21") (name "GND_IN") (class "Default")
      (node (ref "C11") (pin "1") (pinfunction "C_1") (pintype "passive"))
      (node (ref "C12") (pin "1") (pinfunction "C_1") (pintype "passive"))
      (node (ref "C13") (pin "2") (pinfunction "2_2") (pintype "passive"))
      (node (ref "C14") (pin "1") (pinfunction "C_1") (pintype "passive"))
      (node (ref "C15") (pin "1") (pinfunction "C_1") (pintype "passive"))
      (node (ref "C16") (pin "2") (pinfunction "2_2") (pintype "passive"))
      (node (ref "C17") (pin "2") (pinfunction "2_2") (pintype "passive"))
      (node (ref "C18") (pin "2") (pinfunction "2_2") (pintype "passive"))
      (node (ref "C19") (pin "2") (pinfunction "2_2") (pintype "passive"))
      (node (ref "C20") (pin "2") (pinfunction "2_2") (pintype "passive"))
      (node (ref "C21") (pin "2") (pinfunction "2_2") (pintype "passive"))
      (node (ref "C24") (pin "2") (pinfunction "2_2") (pintype "passive"))
      (node (ref "C25") (pin "1") (pinfunction "C_1") (pintype "passive"))
      (node (ref "C26") (pin "2") (pinfunction "2_2") (pintype "passive"))
      (node (ref "C27") (pin "1") (pinfunction "C_1") (pintype "passive"))
      (node (ref "C28") (pin "1") (pinfunction "C_1") (pintype "passive"))
      (node (ref "C29") (pin "1") (pinfunction "C_1") (pintype "passive"))
      (node (ref "C30") (pin "2") (pinfunction "2_2") (pintype "passive"))
      (node (ref "C31") (pin "2") (pinfunction "2_2") (pintype "passive"))
      (node (ref "C32") (pin "2") (pinfunction "2_2") (pintype "passive"))
      (node (ref "C33") (pin "2") (pinfunction "2_2") (pintype "passive"))
      (node (ref "C5") (pin "1") (pinfunction "1_1") (pintype "passive"))
      (node (ref "C7") (pin "1") (pinfunction "1_1") (pintype "passive"))
      (node (ref "C8") (pin "1") (pinfunction "C_1") (pintype "passive"))
      (node (ref "D11") (pin "2") (pinfunction "A_2") (pintype "passive"))
      (node (ref "D17") (pin "2") (pinfunction "A_2") (pintype "passive"))
      (node (ref "D9") (pin "1") (pinfunction "1_1") (pintype "passive"))
      (node (ref "IC3") (pin "2") (pinfunction "GND_2") (pintype "passive"))
      (node (ref "J2") (pin "1") (pinfunction "1_1") (pintype "passive"))
      (node (ref "PS1") (pin "2") (pinfunction "-VIN_1_2") (pintype "passive"))
      (node (ref "PS1") (pin "3") (pinfunction "-VIN_2_3") (pintype "passive"))
      (node (ref "PS2") (pin "2") (pinfunction "-VIN_2") (pintype "passive"))
      (node (ref "PS3") (pin "2") (pinfunction "-VIN_2") (pintype "passive"))
      (node (ref "R16") (pin "1") (pinfunction "1_1") (pintype "passive"))
      (node (ref "R17") (pin "1") (pinfunction "1_1") (pintype "passive"))
      (node (ref "R19") (pin "1") (pinfunction "1_1") (pintype "passive"))
      (node (ref "R23") (pin "1") (pinfunction "1_1") (pintype "passive"))
      (node (ref "R24") (pin "1") (pinfunction "1_1") (pintype "passive"))
      (node (ref "R67") (pin "1") (pinfunction "1_1") (pintype "passive"))
      (node (ref "R68") (pin "1") (pinfunction "1_1") (pintype "passive"))
      (node (ref "R69") (pin "1") (pinfunction "1_1") (pintype "passive"))
      (node (ref "U1") (pin "3") (pinfunction "GROUND_3") (pintype "power_in"))
      (node (ref "U1") (pin "5") (pinfunction "~{ON}/OFF_5") (pintype "input"))
      (node (ref "U1") (pin "6") (pinfunction "GND_6") (pintype "power_in"))
      (node (ref "U2") (pin "3") (pinfunction "GROUND_3") (pintype "power_in"))
      (node (ref "U2") (pin "5") (pinfunction "~{ON}/OFF_5") (pintype "input"))
      (node (ref "U2") (pin "6") (pinfunction "GND_6") (pintype "power_in"))
    )
    (net (code "22") (name "GND_uc") (class "Default")
      (node (ref "C10") (pin "1") (pinfunction "C_1") (pintype "passive"))
      (node (ref "C34") (pin "2") (pinfunction "2_2") (pintype "passive"))
      (node (ref "C35") (pin "2") (pinfunction "2_2") (pintype "passive"))
      (node (ref "C6") (pin "1") (pinfunction "1_1") (pintype "passive"))
      (node (ref "C9") (pin "1") (pinfunction "C_1") (pintype "passive"))
      (node (ref "D19") (pin "2") (pinfunction "A_2") (pintype "passive"))
      (node (ref "LED_1") (pin "2") (pinfunction "K_2") (pintype "passive"))
      (node (ref "PS1") (pin "16") (pinfunction "-VOUT_16") (pintype "passive"))
      (node (ref "R14") (pin "1") (pinfunction "1_1") (pintype "passive"))
      (node (ref "U3") (pin "1") (pinfunction "GND_1") (pintype "power_in"))
    )
    (net (code "23") (name "Net-(D12-C)") (class "Default")
      (node (ref "D12") (pin "1") (pinfunction "C_1") (pintype "passive"))
      (node (ref "R16") (pin "2") (pinfunction "2_2") (pintype "passive"))
    )
    (net (code "24") (name "Net-(D13-C)") (class "Default")
      (node (ref "D13") (pin "1") (pinfunction "C_1") (pintype "passive"))
      (node (ref "R14") (pin "2") (pinfunction "2_2") (pintype "passive"))
    )
    (net (code "25") (name "Net-(D15-C)") (class "Default")
      (node (ref "D15") (pin "1") (pinfunction "C_1") (pintype "passive"))
      (node (ref "R23") (pin "2") (pinfunction "2_2") (pintype "passive"))
    )
    (net (code "26") (name "Net-(LED_1-A)") (class "Default")
      (node (ref "LED_1") (pin "1") (pinfunction "A_1") (pintype "passive"))
      (node (ref "R21") (pin "2") (pinfunction "2_2") (pintype "passive"))
    )
    (net (code "27") (name "pre_+3.3") (class "Default")
      (node (ref "C35") (pin "1") (pinfunction "1_1") (pintype "passive"))
      (node (ref "D18") (pin "1") (pinfunction "A_1") (pintype "passive"))
      (node (ref "D19") (pin "1") (pinfunction "C_1") (pintype "passive"))
      (node (ref "FU1") (pin "1") (pinfunction "1_1") (pintype "passive"))
      (node (ref "U3") (pin "2") (pinfunction "OUT_2") (pintype "power_in"))
      (node (ref "U3") (pin "4") (pinfunction "TAB_4") (pintype "power_in"))
    )
    (net (code "28") (name "unconnected-(PS1-NC-Pad11)") (class "Default")
      (node (ref "PS1") (pin "11") (pinfunction "NC_11") (pintype "passive+no_connect"))
    )
  )
)
